# Expansion.net
KiCad netlist of a schematic drawn in Altium Designer
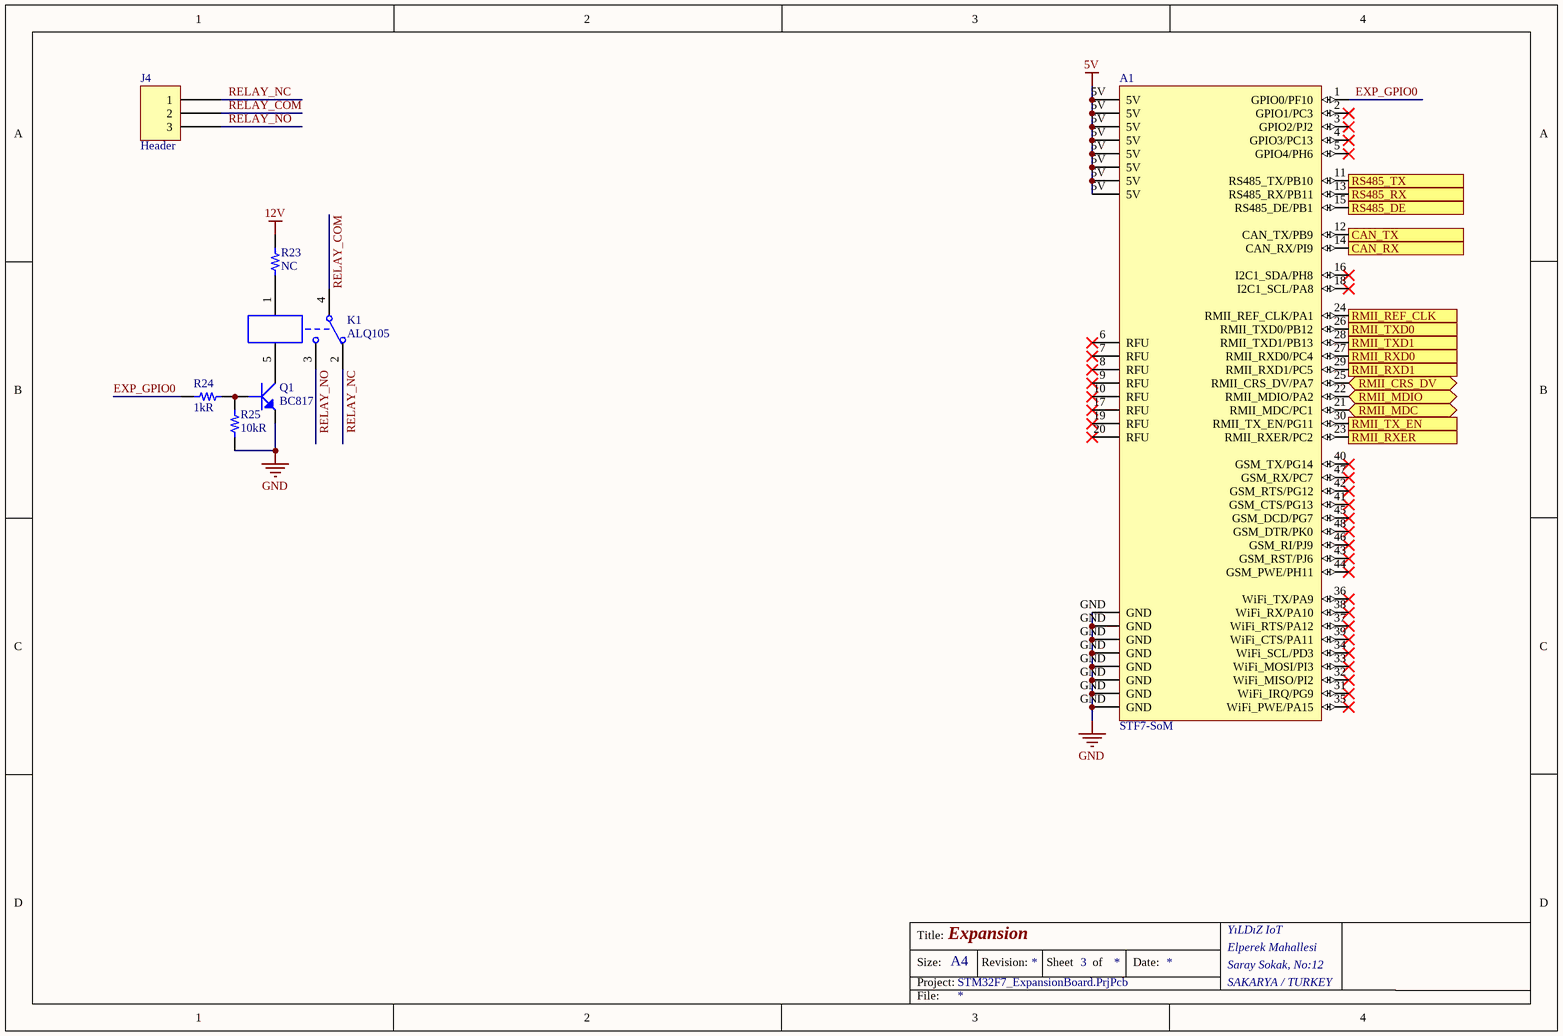
[diagram p0: Expansion.SchDoc]

(export (version "E")
  (design (tool "Eeschema 10.0.6"))
  (components
    (comp (ref "A1")
      (value "STF7-SoM")
      (footprint "STF7-SoM")
      (description "STM32F7 System On Module")
      (libsource (lib "yildizIoT Library") (part "STF7-SoM"))
    )
    (comp (ref "J4")
      (value "Header")
      (footprint "TE 282834-3")
      (libsource (lib "yildizIoT Library") (part "3 Pin"))
    )
    (comp (ref "K1")
      (value "ALQ105")
      (footprint "ALQ105")
      (description "Relay or Contactor")
      (fields (field (name "MANUFACTURER") "Panasonic"))
      (libsource (lib "yildizIoT Library") (part "Relay SPDT"))
    )
    (comp (ref "Q1")
      (value "BC817")
      (footprint "SOT23-3")
      (description "Transistor, BC817")
      (fields
        (field (name "MANUFACTURER") "ON Semiconductor")
        (field (name "MANUFACTURER PART NUMBER") "BC817-16LT1G")
      )
      (libsource (lib "MuhammetLib") (part "BC817"))
    )
    (comp (ref "R23")
      (value "NC")
      (footprint "RES 0603/1608")
      (description "Ceramic, SMT Capacitor")
      (libsource (lib "yildizIoT Library") (part "Resistor_Chip"))
    )
    (comp (ref "R24")
      (value "1kR")
      (footprint "RES 0603/1608")
      (description "Ceramic, SMT Capacitor")
      (fields (field (name "MANUFACTURER") "Rohm") (field (name "MANUFACTURER PART NUMBER") "ESR03EZPJ102"))
      (libsource (lib "yildizIoT Library") (part "Resistor_Chip"))
    )
    (comp (ref "R25")
      (value "10kR")
      (footprint "RES 0603/1608")
      (description "Ceramic, SMT Capacitor")
      (fields
        (field (name "MANUFACTURER") "Stackpole Electronics")
        (field (name "MANUFACTURER PART NUMBER") "RNCP0603FTD10K0")
      )
      (libsource (lib "yildizIoT Library") (part "Resistor_Chip"))
    )
  )
  (nets
    (net (code "1") (name "/CAN_RX") (class "Default")
      (node (ref "A1") (pin "14") (pinfunction "CAN_RX/PI9_14") (pintype "bidirectional"))
    )
    (net (code "2") (name "/CAN_TX") (class "Default")
      (node (ref "A1") (pin "12") (pinfunction "CAN_TX/PB9_12") (pintype "bidirectional"))
    )
    (net (code "3") (name "/EXP_GPIO0") (class "Default")
      (node (ref "A1") (pin "1") (pinfunction "GPIO0/PF10_1") (pintype "bidirectional"))
      (node (ref "R24") (pin "2") (pinfunction "2_2") (pintype "passive"))
    )
    (net (code "4") (name "/RELAY_COM") (class "Default")
      (node (ref "J4") (pin "2") (pinfunction "2_2") (pintype "passive"))
      (node (ref "K1") (pin "4") (pinfunction "COM_4") (pintype "passive"))
    )
    (net (code "5") (name "/RELAY_NC") (class "Default")
      (node (ref "J4") (pin "1") (pinfunction "1_1") (pintype "passive"))
      (node (ref "K1") (pin "2") (pinfunction "NC_2") (pintype "passive"))
    )
    (net (code "6") (name "/RELAY_NO") (class "Default")
      (node (ref "J4") (pin "3") (pinfunction "3_3") (pintype "passive"))
      (node (ref "K1") (pin "3") (pinfunction "NO_3") (pintype "passive"))
    )
    (net (code "7") (name "/RMII_CRS_DV") (class "Default")
      (node (ref "A1") (pin "25") (pinfunction "RMII_CRS_DV/PA7_25") (pintype "bidirectional"))
    )
    (net (code "8") (name "/RMII_MDC") (class "Default")
      (node (ref "A1") (pin "21") (pinfunction "RMII_MDC/PC1_21") (pintype "bidirectional"))
    )
    (net (code "9") (name "/RMII_MDIO") (class "Default")
      (node (ref "A1") (pin "22") (pinfunction "RMII_MDIO/PA2_22") (pintype "bidirectional"))
    )
    (net (code "10") (name "/RMII_REF_CLK") (class "Default")
      (node (ref "A1") (pin "24") (pinfunction "RMII_REF_CLK/PA1_24") (pintype "bidirectional"))
    )
    (net (code "11") (name "/RMII_RXD0") (class "Default")
      (node (ref "A1") (pin "27") (pinfunction "RMII_RXD0/PC4_27") (pintype "bidirectional"))
    )
    (net (code "12") (name "/RMII_RXD1") (class "Default")
      (node (ref "A1") (pin "29") (pinfunction "RMII_RXD1/PC5_29") (pintype "bidirectional"))
    )
    (net (code "13") (name "/RMII_RXER") (class "Default")
      (node (ref "A1") (pin "23") (pinfunction "RMII_RXER/PC2_23") (pintype "bidirectional"))
    )
    (net (code "14") (name "/RMII_TXD0") (class "Default")
      (node (ref "A1") (pin "26") (pinfunction "RMII_TXD0/PB12_26") (pintype "bidirectional"))
    )
    (net (code "15") (name "/RMII_TXD1") (class "Default")
      (node (ref "A1") (pin "28") (pinfunction "RMII_TXD1/PB13_28") (pintype "bidirectional"))
    )
    (net (code "16") (name "/RMII_TX_EN") (class "Default")
      (node (ref "A1") (pin "30") (pinfunction "RMII_TX_EN/PG11_30") (pintype "bidirectional"))
    )
    (net (code "17") (name "/RS485_DE") (class "Default")
      (node (ref "A1") (pin "15") (pinfunction "RS485_DE/PB1_15") (pintype "bidirectional"))
    )
    (net (code "18") (name "/RS485_RX") (class "Default")
      (node (ref "A1") (pin "13") (pinfunction "RS485_RX/PB11_13") (pintype "bidirectional"))
    )
    (net (code "19") (name "/RS485_TX") (class "Default")
      (node (ref "A1") (pin "11") (pinfunction "RS485_TX/PB10_11") (pintype "bidirectional"))
    )
    (net (code "20") (name "5V") (class "Default")
      (node (ref "A1") (pin "5V") (pinfunction "5V_5V") (pintype "power_in"))
    )
    (net (code "21") (name "12V") (class "Default")
      (node (ref "R23") (pin "2") (pinfunction "2_2") (pintype "passive"))
    )
    (net (code "22") (name "GND") (class "Default")
      (node (ref "A1") (pin "GND") (pinfunction "GND_GND") (pintype "power_in"))
      (node (ref "Q1") (pin "2") (pinfunction "E_2") (pintype "passive"))
      (node (ref "R25") (pin "2") (pinfunction "2_2") (pintype "passive"))
    )
    (net (code "23") (name "Net-(K1-COIL-Pad1)") (class "Default")
      (node (ref "K1") (pin "1") (pinfunction "COIL_1") (pintype "passive"))
      (node (ref "R23") (pin "1") (pinfunction "1_1") (pintype "passive"))
    )
    (net (code "24") (name "Net-(Q1-B)") (class "Default")
      (node (ref "Q1") (pin "1") (pinfunction "B_1") (pintype "passive"))
      (node (ref "R24") (pin "1") (pinfunction "1_1") (pintype "passive"))
      (node (ref "R25") (pin "1") (pinfunction "1_1") (pintype "passive"))
    )
    (net (code "25") (name "Net-(Q1-C)") (class "Default")
      (node (ref "K1") (pin "5") (pinfunction "COIL_5") (pintype "passive"))
      (node (ref "Q1") (pin "3") (pinfunction "C_3") (pintype "passive"))
    )
    (net (code "26") (name "unconnected-(A1-GPIO1{slash}PC3-Pad2)") (class "Default")
      (node (ref "A1") (pin "2") (pinfunction "GPIO1/PC3_2") (pintype "bidirectional+no_connect"))
    )
    (net (code "27") (name "unconnected-(A1-GPIO2{slash}PJ2-Pad3)") (class "Default")
      (node (ref "A1") (pin "3") (pinfunction "GPIO2/PJ2_3") (pintype "bidirectional+no_connect"))
    )
    (net (code "28") (name "unconnected-(A1-GPIO3{slash}PC13-Pad4)") (class "Default")
      (node (ref "A1") (pin "4") (pinfunction "GPIO3/PC13_4") (pintype "bidirectional+no_connect"))
    )
    (net (code "29") (name "unconnected-(A1-GPIO4{slash}PH6-Pad5)") (class "Default")
      (node (ref "A1") (pin "5") (pinfunction "GPIO4/PH6_5") (pintype "bidirectional+no_connect"))
    )
    (net (code "30") (name "unconnected-(A1-GSM_CTS{slash}PG13-Pad41)") (class "Default")
      (node (ref "A1") (pin "41") (pinfunction "GSM_CTS/PG13_41") (pintype "bidirectional+no_connect"))
    )
    (net (code "31") (name "unconnected-(A1-GSM_DCD{slash}PG7-Pad45)") (class "Default")
      (node (ref "A1") (pin "45") (pinfunction "GSM_DCD/PG7_45") (pintype "bidirectional+no_connect"))
    )
    (net (code "32") (name "unconnected-(A1-GSM_DTR{slash}PK0-Pad48)") (class "Default")
      (node (ref "A1") (pin "48") (pinfunction "GSM_DTR/PK0_48") (pintype "bidirectional+no_connect"))
    )
    (net (code "33") (name "unconnected-(A1-GSM_PWE{slash}PH11-Pad44)") (class "Default")
      (node (ref "A1") (pin "44") (pinfunction "GSM_PWE/PH11_44") (pintype "bidirectional+no_connect"))
    )
    (net (code "34") (name "unconnected-(A1-GSM_RI{slash}PJ9-Pad46)") (class "Default")
      (node (ref "A1") (pin "46") (pinfunction "GSM_RI/PJ9_46") (pintype "bidirectional+no_connect"))
    )
    (net (code "35") (name "unconnected-(A1-GSM_RST{slash}PJ6-Pad43)") (class "Default")
      (node (ref "A1") (pin "43") (pinfunction "GSM_RST/PJ6_43") (pintype "bidirectional+no_connect"))
    )
    (net (code "36") (name "unconnected-(A1-GSM_RTS{slash}PG12-Pad42)") (class "Default")
      (node (ref "A1") (pin "42") (pinfunction "GSM_RTS/PG12_42") (pintype "bidirectional+no_connect"))
    )
    (net (code "37") (name "unconnected-(A1-GSM_RX{slash}PC7-Pad47)") (class "Default")
      (node (ref "A1") (pin "47") (pinfunction "GSM_RX/PC7_47") (pintype "bidirectional+no_connect"))
    )
    (net (code "38") (name "unconnected-(A1-GSM_TX{slash}PG14-Pad40)") (class "Default")
      (node (ref "A1") (pin "40") (pinfunction "GSM_TX/PG14_40") (pintype "bidirectional+no_connect"))
    )
    (net (code "39") (name "unconnected-(A1-I2C1_SCL{slash}PA8-Pad18)") (class "Default")
      (node (ref "A1") (pin "18") (pinfunction "I2C1_SCL/PA8_18") (pintype "bidirectional+no_connect"))
    )
    (net (code "40") (name "unconnected-(A1-I2C1_SDA{slash}PH8-Pad16)") (class "Default")
      (node (ref "A1") (pin "16") (pinfunction "I2C1_SDA/PH8_16") (pintype "bidirectional+no_connect"))
    )
    (net (code "41") (name "unconnected-(A1-RFU-Pad6)") (class "Default")
      (node (ref "A1") (pin "6") (pinfunction "RFU_6") (pintype "passive+no_connect"))
    )
    (net (code "42") (name "unconnected-(A1-RFU-Pad7)") (class "Default")
      (node (ref "A1") (pin "7") (pinfunction "RFU_7") (pintype "passive+no_connect"))
    )
    (net (code "43") (name "unconnected-(A1-RFU-Pad8)") (class "Default")
      (node (ref "A1") (pin "8") (pinfunction "RFU_8") (pintype "passive+no_connect"))
    )
    (net (code "44") (name "unconnected-(A1-RFU-Pad9)") (class "Default")
      (node (ref "A1") (pin "9") (pinfunction "RFU_9") (pintype "passive+no_connect"))
    )
    (net (code "45") (name "unconnected-(A1-RFU-Pad10)") (class "Default")
      (node (ref "A1") (pin "10") (pinfunction "RFU_10") (pintype "passive+no_connect"))
    )
    (net (code "46") (name "unconnected-(A1-RFU-Pad17)") (class "Default")
      (node (ref "A1") (pin "17") (pinfunction "RFU_17") (pintype "passive+no_connect"))
    )
    (net (code "47") (name "unconnected-(A1-RFU-Pad19)") (class "Default")
      (node (ref "A1") (pin "19") (pinfunction "RFU_19") (pintype "passive+no_connect"))
    )
    (net (code "48") (name "unconnected-(A1-RFU-Pad20)") (class "Default")
      (node (ref "A1") (pin "20") (pinfunction "RFU_20") (pintype "passive+no_connect"))
    )
    (net (code "49") (name "unconnected-(A1-WiFi_CTS{slash}PA11-Pad39)") (class "Default")
      (node (ref "A1") (pin "39") (pinfunction "WiFi_CTS/PA11_39") (pintype "bidirectional+no_connect"))
    )
    (net (code "50") (name "unconnected-(A1-WiFi_IRQ{slash}PG9-Pad31)") (class "Default")
      (node (ref "A1") (pin "31") (pinfunction "WiFi_IRQ/PG9_31") (pintype "bidirectional+no_connect"))
    )
    (net (code "51") (name "unconnected-(A1-WiFi_MISO{slash}PI2-Pad32)") (class "Default")
      (node (ref "A1") (pin "32") (pinfunction "WiFi_MISO/PI2_32") (pintype "bidirectional+no_connect"))
    )
    (net (code "52") (name "unconnected-(A1-WiFi_MOSI{slash}PI3-Pad33)") (class "Default")
      (node (ref "A1") (pin "33") (pinfunction "WiFi_MOSI/PI3_33") (pintype "bidirectional+no_connect"))
    )
    (net (code "53") (name "unconnected-(A1-WiFi_PWE{slash}PA15-Pad35)") (class "Default")
      (node (ref "A1") (pin "35") (pinfunction "WiFi_PWE/PA15_35") (pintype "bidirectional+no_connect"))
    )
    (net (code "54") (name "unconnected-(A1-WiFi_RTS{slash}PA12-Pad37)") (class "Default")
      (node (ref "A1") (pin "37") (pinfunction "WiFi_RTS/PA12_37") (pintype "bidirectional+no_connect"))
    )
    (net (code "55") (name "unconnected-(A1-WiFi_RX{slash}PA10-Pad38)") (class "Default")
      (node (ref "A1") (pin "38") (pinfunction "WiFi_RX/PA10_38") (pintype "bidirectional+no_connect"))
    )
    (net (code "56") (name "unconnected-(A1-WiFi_SCL{slash}PD3-Pad34)") (class "Default")
      (node (ref "A1") (pin "34") (pinfunction "WiFi_SCL/PD3_34") (pintype "bidirectional+no_connect"))
    )
    (net (code "57") (name "unconnected-(A1-WiFi_TX{slash}PA9-Pad36)") (class "Default")
      (node (ref "A1") (pin "36") (pinfunction "WiFi_TX/PA9_36") (pintype "bidirectional+no_connect"))
    )
  )
)
